# 08_CAN_Interface.net
KiCad netlist of a schematic drawn in Altium Designer
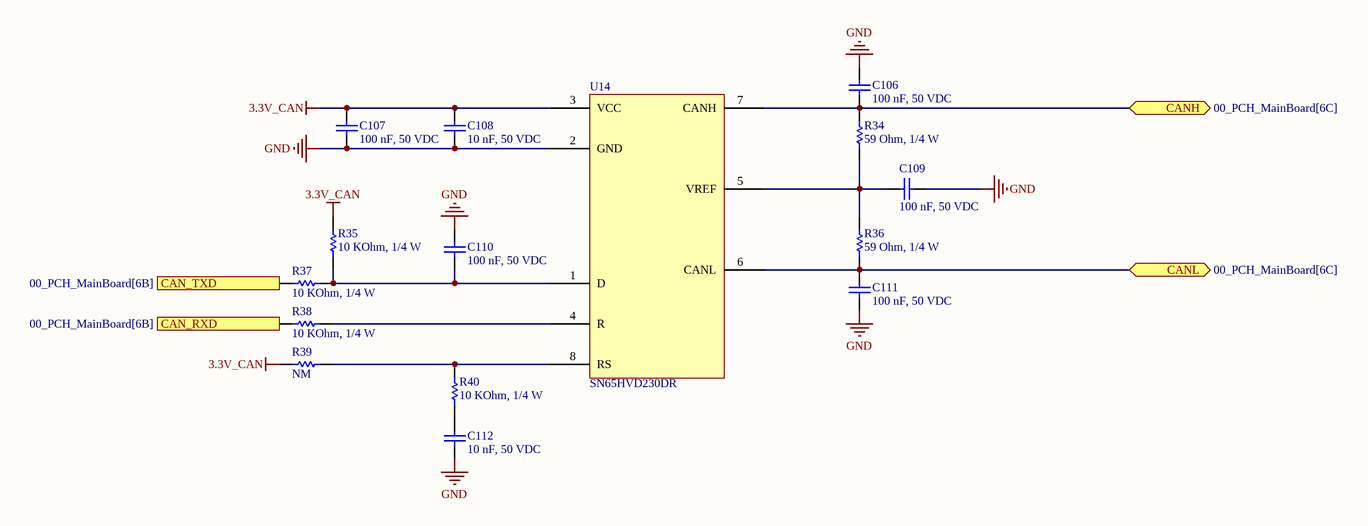
[diagram p0: 08_CAN_Interface.SchDoc]

(export (version "E")
  (design (tool "Eeschema 10.0.6"))
  (components
    (comp (ref "C106")
      (value "100 nF, 50 VDC")
      (footprint "CAP_0603")
      (description "CAP, size 0603, 100 nF, 50 VDC")
      (fields (field (name "TOLERANCE") "+/-10%"))
      (libsource (lib "Altium_Ceramic_Cap") (part "0106031041050"))
    )
    (comp (ref "C107")
      (value "100 nF, 50 VDC")
      (footprint "CAP_0603")
      (description "CAP, size 0603, 100 nF, 50 VDC")
      (fields (field (name "TOLERANCE") "+/-10%"))
      (libsource (lib "Altium_Ceramic_Cap") (part "0106031041050"))
    )
    (comp (ref "C108")
      (value "10 nF, 50 VDC")
      (footprint "CAP_0603")
      (description "CAP, size 0603, 10 nF, 50 VDC")
      (fields (field (name "TOLERANCE") "+/-5%"))
      (libsource (lib "Altium_Ceramic_Cap") (part "0106031030550"))
    )
    (comp (ref "C109")
      (value "100 nF, 50 VDC")
      (footprint "CAP_0603")
      (description "CAP, size 0603, 100 nF, 50 VDC")
      (fields (field (name "TOLERANCE") "+/-10%"))
      (libsource (lib "Altium_Ceramic_Cap") (part "0106031041050"))
    )
    (comp (ref "C110")
      (value "100 nF, 50 VDC")
      (footprint "CAP_0603")
      (description "CAP, size 0603, 100 nF, 50 VDC")
      (fields (field (name "TOLERANCE") "+/-10%"))
      (libsource (lib "Altium_Ceramic_Cap") (part "0106031041050"))
    )
    (comp (ref "C111")
      (value "100 nF, 50 VDC")
      (footprint "CAP_0603")
      (description "CAP, size 0603, 100 nF, 50 VDC")
      (fields (field (name "TOLERANCE") "+/-10%"))
      (libsource (lib "Altium_Ceramic_Cap") (part "0106031041050"))
    )
    (comp (ref "C112")
      (value "10 nF, 50 VDC")
      (footprint "CAP_0603")
      (description "CAP, size 0603, 10 nF, 50 VDC")
      (fields (field (name "TOLERANCE") "+/-5%"))
      (libsource (lib "Altium_Ceramic_Cap") (part "0106031030550"))
    )
    (comp (ref "R34")
      (value "59 Ohm, 1/4 W")
      (footprint "resistor_0603")
      (description "RES, size 0603, 59 Ohm, 1/4 W")
      (libsource (lib "Altium_Resistor") (part "0006035901"))
    )
    (comp (ref "R35")
      (value "10 KOhm, 1/4 W")
      (footprint "resistor_0603")
      (description "RES, size 0603, 10 KOhm, 1/4 W")
      (libsource (lib "Altium_Resistor") (part "0006031031"))
    )
    (comp (ref "R36")
      (value "59 Ohm, 1/4 W")
      (footprint "resistor_0603")
      (description "RES, size 0603, 59 Ohm, 1/4 W")
      (libsource (lib "Altium_Resistor") (part "0006035901"))
    )
    (comp (ref "R37")
      (value "10 KOhm, 1/4 W")
      (footprint "resistor_0603")
      (description "RES, size 0603, 10 KOhm, 1/4 W")
      (libsource (lib "Altium_Resistor") (part "0006031031"))
    )
    (comp (ref "R38")
      (value "10 KOhm, 1/4 W")
      (footprint "resistor_0603")
      (description "RES, size 0603, 10 KOhm, 1/4 W")
      (libsource (lib "Altium_Resistor") (part "0006031031"))
    )
    (comp (ref "R39")
      (value "NM")
      (footprint "resistor_0603")
      (description "RES, size 0603, NM")
      (libsource (lib "Altium_Resistor") (part "000603_NM"))
    )
    (comp (ref "R40")
      (value "10 KOhm, 1/4 W")
      (footprint "resistor_0603")
      (description "RES, size 0603, 10 KOhm, 1/4 W")
      (libsource (lib "Altium_Resistor") (part "0006031031"))
    )
    (comp (ref "U14")
      (value "SN65HVD230DR")
      (footprint "SN65HVD230")
      (description "CAN Interface IC STANDBY MODE")
      (fields (field (name "MANUFACTURER") "Texas Instruments"))
      (libsource (lib "CAN") (part "SN65HVD230DR"))
    )
  )
  (nets
    (net (code "1") (name "/CANH") (class "Default")
      (node (ref "C106") (pin "1") (pinfunction "1_1") (pintype "passive"))
      (node (ref "R34") (pin "2") (pinfunction "2_2") (pintype "passive"))
      (node (ref "U14") (pin "7") (pinfunction "CANH_7") (pintype "passive"))
    )
    (net (code "2") (name "/CANL") (class "Default")
      (node (ref "C111") (pin "2") (pinfunction "2_2") (pintype "passive"))
      (node (ref "R36") (pin "1") (pinfunction "1_1") (pintype "passive"))
      (node (ref "U14") (pin "6") (pinfunction "CANL_6") (pintype "passive"))
    )
    (net (code "3") (name "/CAN_RXD") (class "Default")
      (node (ref "R38") (pin "1") (pinfunction "1_1") (pintype "passive"))
    )
    (net (code "4") (name "/CAN_TXD") (class "Default")
      (node (ref "R37") (pin "1") (pinfunction "1_1") (pintype "passive"))
    )
    (net (code "5") (name "3.3V_CAN") (class "Default")
      (node (ref "C107") (pin "2") (pinfunction "2_2") (pintype "passive"))
      (node (ref "C108") (pin "2") (pinfunction "2_2") (pintype "passive"))
      (node (ref "R35") (pin "1") (pinfunction "1_1") (pintype "passive"))
      (node (ref "R39") (pin "1") (pinfunction "1_1") (pintype "passive"))
      (node (ref "U14") (pin "3") (pinfunction "VCC_3") (pintype "passive"))
    )
    (net (code "6") (name "GND") (class "Default")
      (node (ref "C106") (pin "2") (pinfunction "2_2") (pintype "passive"))
      (node (ref "C107") (pin "1") (pinfunction "1_1") (pintype "passive"))
      (node (ref "C108") (pin "1") (pinfunction "1_1") (pintype "passive"))
      (node (ref "C109") (pin "2") (pinfunction "2_2") (pintype "passive"))
      (node (ref "C110") (pin "2") (pinfunction "2_2") (pintype "passive"))
      (node (ref "C111") (pin "1") (pinfunction "1_1") (pintype "passive"))
      (node (ref "C112") (pin "1") (pinfunction "1_1") (pintype "passive"))
      (node (ref "U14") (pin "2") (pinfunction "GND_2") (pintype "passive"))
    )
    (net (code "7") (name "Net-(C112-Pad2)") (class "Default")
      (node (ref "C112") (pin "2") (pinfunction "2_2") (pintype "passive"))
      (node (ref "R40") (pin "1") (pinfunction "1_1") (pintype "passive"))
    )
    (net (code "8") (name "Net-(U14-D)") (class "Default")
      (node (ref "C110") (pin "1") (pinfunction "1_1") (pintype "passive"))
      (node (ref "R35") (pin "2") (pinfunction "2_2") (pintype "passive"))
      (node (ref "R37") (pin "2") (pinfunction "2_2") (pintype "passive"))
      (node (ref "U14") (pin "1") (pinfunction "D_1") (pintype "passive"))
    )
    (net (code "9") (name "Net-(U14-R)") (class "Default")
      (node (ref "R38") (pin "2") (pinfunction "2_2") (pintype "passive"))
      (node (ref "U14") (pin "4") (pinfunction "R_4") (pintype "passive"))
    )
    (net (code "10") (name "Net-(U14-RS)") (class "Default")
      (node (ref "R39") (pin "2") (pinfunction "2_2") (pintype "passive"))
      (node (ref "R40") (pin "2") (pinfunction "2_2") (pintype "passive"))
      (node (ref "U14") (pin "8") (pinfunction "RS_8") (pintype "passive"))
    )
    (net (code "11") (name "Net-(U14-VREF)") (class "Default")
      (node (ref "C109") (pin "1") (pinfunction "1_1") (pintype "passive"))
      (node (ref "R34") (pin "1") (pinfunction "1_1") (pintype "passive"))
      (node (ref "R36") (pin "2") (pinfunction "2_2") (pintype "passive"))
      (node (ref "U14") (pin "5") (pinfunction "VREF_5") (pintype "passive"))
    )
  )
)
